# Power.net
KiCad netlist of a schematic drawn in Altium Designer
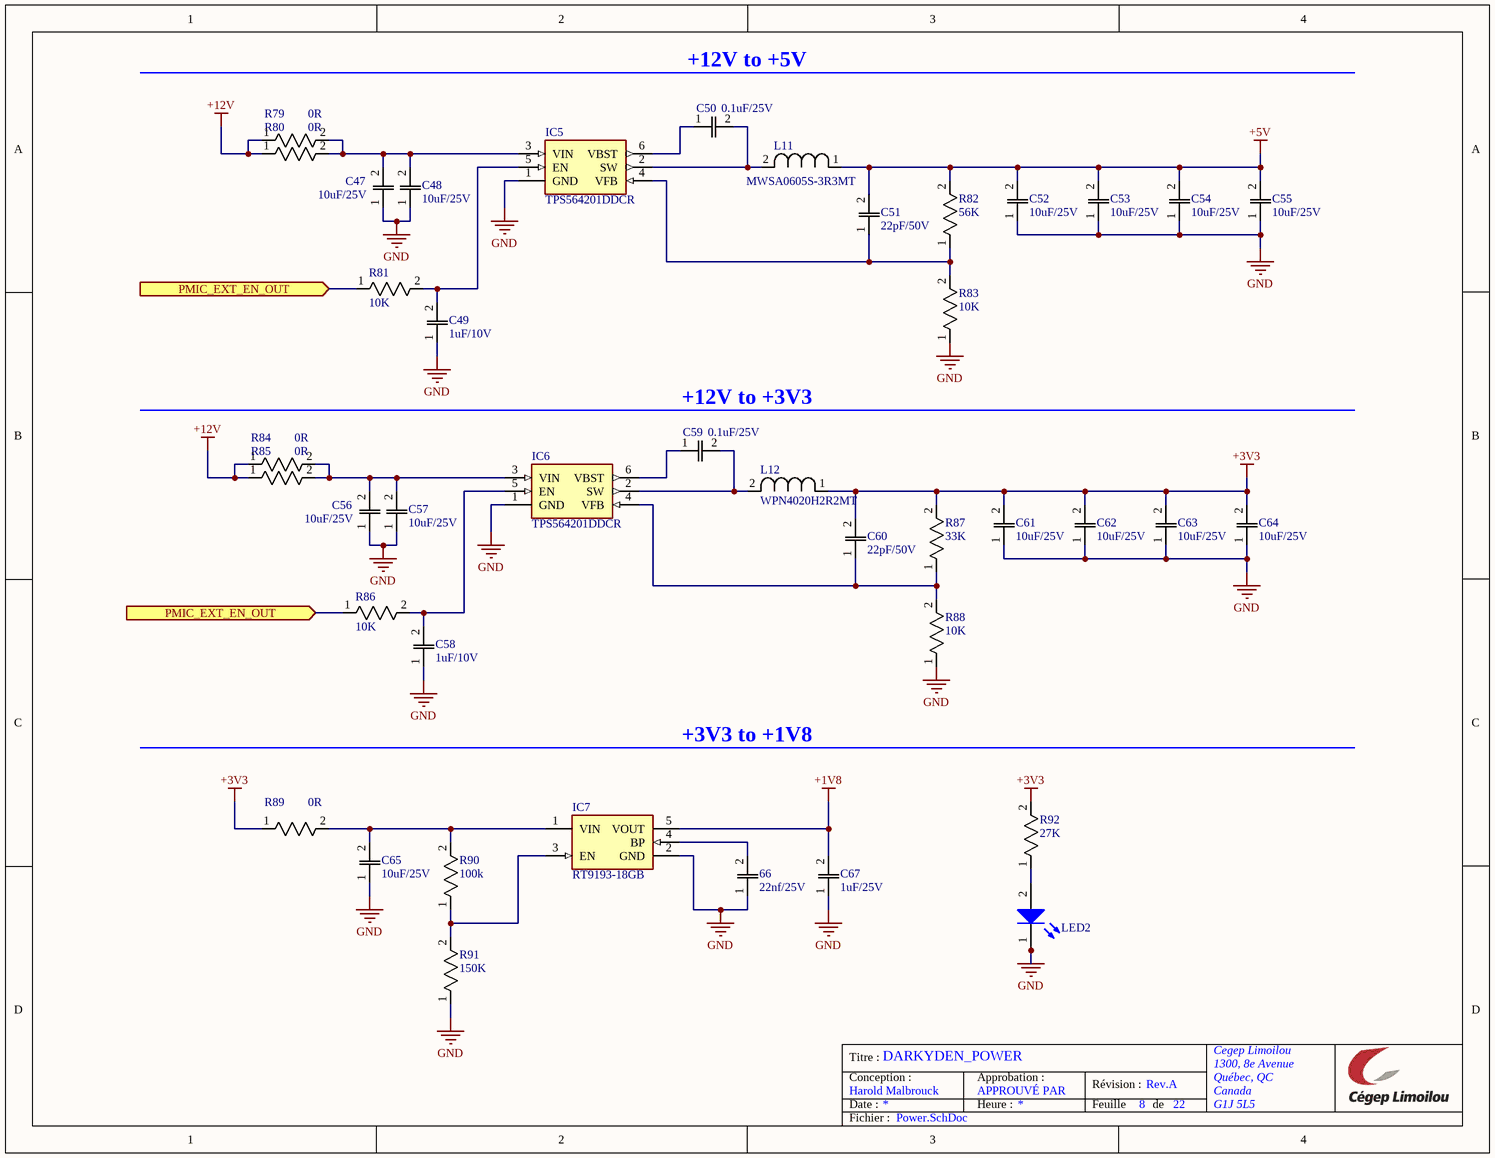
[diagram p0: Power.SchDoc]

(export (version "E")
  (design (tool "Eeschema 10.0.6"))
  (components
    (comp (ref "66")
      (value "22nf/25V")
      (footprint "SamacSys:C0805")
      (description "22nF, 25 V, 0805 [2012 Metric], 5%, C0G / NP0")
      (fields
        (field (name "MANUFACTURER_PART_NUMBER") "C0805C223J3GACTU")
        (field (name "MANUFACTURER") "KEMET")
      )
      (libsource (lib "SamacSys") (part "C0805C223J3GACTU"))
    )
    (comp (ref "C47")
      (value "10uF/25V")
      (footprint "CAPC220145_88N_KEM")
      (description "10uF / 25 VDC, +85degC, X5R Dielec, +/-10% ¦ KEMET C0805C106K3PACTU 0805")
      (fields
        (field (name "MANUFACTURER") "KEMET")
        (field (name "MANUFACTURER PART NUMBER") "C0805C106K3PACTU")
      )
      (libsource (lib "C0805C106K3PACTU") (part "C0805C106K3PACTU"))
    )
    (comp (ref "C48")
      (value "10uF/25V")
      (footprint "CAPC220145_88N_KEM")
      (description "10uF / 25 VDC, +85degC, X5R Dielec, +/-10% ¦ KEMET C0805C106K3PACTU 0805")
      (fields
        (field (name "MANUFACTURER") "KEMET")
        (field (name "MANUFACTURER PART NUMBER") "C0805C106K3PACTU")
      )
      (libsource (lib "C0805C106K3PACTU") (part "C0805C106K3PACTU"))
    )
    (comp (ref "C49")
      (value "1uF/10V")
      (footprint "CAPC220145_88N_KEM")
      (description "Multilayer Ceramic Capacitors MLCC - SMD/SMT 10V 1uF X7R 0805 10%")
      (fields
        (field (name "MANUFACTURER") "KEMET")
        (field (name "MANUFACTURER PART NUMBER") "C0805C105K8RACTU")
      )
      (libsource (lib "C0805C105K8RACTU") (part "C0805C105K8RACTU"))
    )
    (comp (ref "C50")
      (value "0.1uF/25V")
      (footprint "CAPC220145_88N_KEM")
      (description "0.1uF 25V X7R 10% SMD 0805 125C Plastic T/R")
      (fields
        (field (name "MANUFACTURER") "KEMET")
        (field (name "MANUFACTURER PART NUMBER") "C0805C104K3RACTU")
      )
      (libsource (lib "C0805C104K3RACTU") (part "C0805C104K3RACTU"))
    )
    (comp (ref "C51")
      (value "22pF/50V")
      (footprint "CAPC220145_88N_KEM")
      (description "Cap Ceramic 22pF 50V X7R 5% Pad SMD 0805 125°C T/R")
      (fields
        (field (name "MANUFACTURER") "KEMET")
        (field (name "MANUFACTURER PART NUMBER") "C0805C220J5RACTU")
      )
      (libsource (lib "C0805C220J5RACTU") (part "C0805C220J5RACTU"))
    )
    (comp (ref "C52")
      (value "10uF/25V")
      (footprint "CAPC220145_88N_KEM")
      (description "10uF / 25 VDC, +85degC, X5R Dielec, +/-10% ¦ KEMET C0805C106K3PACTU 0805")
      (fields
        (field (name "MANUFACTURER") "KEMET")
        (field (name "MANUFACTURER PART NUMBER") "C0805C106K3PACTU")
      )
      (libsource (lib "C0805C106K3PACTU") (part "C0805C106K3PACTU"))
    )
    (comp (ref "C53")
      (value "10uF/25V")
      (footprint "CAPC220145_88N_KEM")
      (description "10uF / 25 VDC, +85degC, X5R Dielec, +/-10% ¦ KEMET C0805C106K3PACTU 0805")
      (fields
        (field (name "MANUFACTURER") "KEMET")
        (field (name "MANUFACTURER PART NUMBER") "C0805C106K3PACTU")
      )
      (libsource (lib "C0805C106K3PACTU") (part "C0805C106K3PACTU"))
    )
    (comp (ref "C54")
      (value "10uF/25V")
      (footprint "CAPC220145_88N_KEM")
      (description "10uF / 25 VDC, +85degC, X5R Dielec, +/-10% ¦ KEMET C0805C106K3PACTU 0805")
      (fields
        (field (name "MANUFACTURER") "KEMET")
        (field (name "MANUFACTURER PART NUMBER") "C0805C106K3PACTU")
      )
      (libsource (lib "C0805C106K3PACTU") (part "C0805C106K3PACTU"))
    )
    (comp (ref "C55")
      (value "10uF/25V")
      (footprint "CAPC220145_88N_KEM")
      (description "10uF / 25 VDC, +85degC, X5R Dielec, +/-10% ¦ KEMET C0805C106K3PACTU 0805")
      (fields
        (field (name "MANUFACTURER") "KEMET")
        (field (name "MANUFACTURER PART NUMBER") "C0805C106K3PACTU")
      )
      (libsource (lib "C0805C106K3PACTU") (part "C0805C106K3PACTU"))
    )
    (comp (ref "C56")
      (value "10uF/25V")
      (footprint "CAPC220145_88N_KEM")
      (description "10uF / 25 VDC, +85degC, X5R Dielec, +/-10% ¦ KEMET C0805C106K3PACTU 0805")
      (fields
        (field (name "MANUFACTURER") "KEMET")
        (field (name "MANUFACTURER PART NUMBER") "C0805C106K3PACTU")
      )
      (libsource (lib "C0805C106K3PACTU") (part "C0805C106K3PACTU"))
    )
    (comp (ref "C57")
      (value "10uF/25V")
      (footprint "CAPC220145_88N_KEM")
      (description "10uF / 25 VDC, +85degC, X5R Dielec, +/-10% ¦ KEMET C0805C106K3PACTU 0805")
      (fields
        (field (name "MANUFACTURER") "KEMET")
        (field (name "MANUFACTURER PART NUMBER") "C0805C106K3PACTU")
      )
      (libsource (lib "C0805C106K3PACTU") (part "C0805C106K3PACTU"))
    )
    (comp (ref "C58")
      (value "1uF/10V")
      (footprint "CAPC220145_88N_KEM")
      (description "Multilayer Ceramic Capacitors MLCC - SMD/SMT 10V 1uF X7R 0805 10%")
      (fields
        (field (name "MANUFACTURER") "KEMET")
        (field (name "MANUFACTURER PART NUMBER") "C0805C105K8RACTU")
      )
      (libsource (lib "C0805C105K8RACTU") (part "C0805C105K8RACTU"))
    )
    (comp (ref "C59")
      (value "0.1uF/25V")
      (footprint "CAPC220145_88N_KEM")
      (description "0.1uF 25V X7R 10% SMD 0805 125C Plastic T/R")
      (fields
        (field (name "MANUFACTURER") "KEMET")
        (field (name "MANUFACTURER PART NUMBER") "C0805C104K3RACTU")
      )
      (libsource (lib "C0805C104K3RACTU") (part "C0805C104K3RACTU"))
    )
    (comp (ref "C60")
      (value "22pF/50V")
      (footprint "CAPC220145_88N_KEM")
      (description "Cap Ceramic 22pF 50V X7R 5% Pad SMD 0805 125°C T/R")
      (fields
        (field (name "MANUFACTURER") "KEMET")
        (field (name "MANUFACTURER PART NUMBER") "C0805C220J5RACTU")
      )
      (libsource (lib "C0805C220J5RACTU") (part "C0805C220J5RACTU"))
    )
    (comp (ref "C61")
      (value "10uF/25V")
      (footprint "CAPC220145_88N_KEM")
      (description "10uF / 25 VDC, +85degC, X5R Dielec, +/-10% ¦ KEMET C0805C106K3PACTU 0805")
      (fields
        (field (name "MANUFACTURER") "KEMET")
        (field (name "MANUFACTURER PART NUMBER") "C0805C106K3PACTU")
      )
      (libsource (lib "C0805C106K3PACTU") (part "C0805C106K3PACTU"))
    )
    (comp (ref "C62")
      (value "10uF/25V")
      (footprint "CAPC220145_88N_KEM")
      (description "10uF / 25 VDC, +85degC, X5R Dielec, +/-10% ¦ KEMET C0805C106K3PACTU 0805")
      (fields
        (field (name "MANUFACTURER") "KEMET")
        (field (name "MANUFACTURER PART NUMBER") "C0805C106K3PACTU")
      )
      (libsource (lib "C0805C106K3PACTU") (part "C0805C106K3PACTU"))
    )
    (comp (ref "C63")
      (value "10uF/25V")
      (footprint "CAPC220145_88N_KEM")
      (description "10uF / 25 VDC, +85degC, X5R Dielec, +/-10% ¦ KEMET C0805C106K3PACTU 0805")
      (fields
        (field (name "MANUFACTURER") "KEMET")
        (field (name "MANUFACTURER PART NUMBER") "C0805C106K3PACTU")
      )
      (libsource (lib "C0805C106K3PACTU") (part "C0805C106K3PACTU"))
    )
    (comp (ref "C64")
      (value "10uF/25V")
      (footprint "CAPC220145_88N_KEM")
      (description "10uF / 25 VDC, +85degC, X5R Dielec, +/-10% ¦ KEMET C0805C106K3PACTU 0805")
      (fields
        (field (name "MANUFACTURER") "KEMET")
        (field (name "MANUFACTURER PART NUMBER") "C0805C106K3PACTU")
      )
      (libsource (lib "C0805C106K3PACTU") (part "C0805C106K3PACTU"))
    )
    (comp (ref "C65")
      (value "10uF/25V")
      (footprint "CAPC220145_88N_KEM")
      (description "10uF / 25 VDC, +85degC, X5R Dielec, +/-10% ¦ KEMET C0805C106K3PACTU 0805")
      (fields
        (field (name "MANUFACTURER") "KEMET")
        (field (name "MANUFACTURER PART NUMBER") "C0805C106K3PACTU")
      )
      (libsource (lib "C0805C106K3PACTU") (part "C0805C106K3PACTU"))
    )
    (comp (ref "C67")
      (value "1uF/25V")
      (footprint "SamacSys:C0805")
      (description "1 µF, 25 V (DC), ±10 %, SMD 0805, X7R, C0805C105K3RAC7800")
      (fields
        (field (name "MANUFACTURER_PART_NUMBER") "C0805C105K3RACTU")
        (field (name "MOUSER PART NUMBER") "80-C0805C105K3R")
      )
      (libsource (lib "SamacSys") (part "C0805C105K3RACTU"))
    )
    (comp (ref "IC5")
      (value "TPS564201DDCR")
      (footprint "SamacSys:SOT95P280X110-6N")
      (fields
        (field (name "MOUSER PART NUMBER") "595-TPS564201DDCR")
        (field (name "MANUFACTURER") "Texas Instruments")
      )
      (libsource (lib "SamacSys") (part "TPS564201DDCR"))
    )
    (comp (ref "IC6")
      (value "TPS564201DDCR")
      (footprint "SamacSys:SOT95P280X110-6N")
      (fields
        (field (name "MOUSER PART NUMBER") "595-TPS564201DDCR")
        (field (name "MANUFACTURER") "Texas Instruments")
      )
      (libsource (lib "SamacSys") (part "TPS564201DDCR"))
    )
    (comp (ref "IC7")
      (value "RT9193-18GB")
      (footprint "SamacSys:SOT94P279X130-5N")
      (description "Linear Voltage Regulator IC Positive Fixed 1.8V Output 300mA SOT-23-5")
      (fields (field (name "MOUSER PART NUMBER") "835-RT9193-18GB"))
      (libsource (lib "SamacSys") (part "RT9193-18GB"))
    )
    (comp (ref "L11")
      (value "MWSA0605S-3R3MT")
      (footprint "IND_MWSA0603S_SNL")
      (description "3.3 µH Shielded Drum Core, Wirewound Inductor 8.5 A 22mOhm Max Nonstandard")
      (libsource (lib "MWSA0603S-XRXMT") (part "MWSA0605S-3R3MT"))
    )
    (comp (ref "L12")
      (value "WPN4020H2R2MT")
      (footprint "IND_WPN4020H_SNL")
      (description "2.2 µH Shielded Drum Core, Wirewound Inductor 4.3 A 48mOhm Max Nonstandard")
      (fields (field (name "MANUFACTURER") "Sunlord"))
      (libsource (lib "WPN4020H2R2MT") (part "WPN4020H2R2MT"))
    )
    (comp (ref "LED2")
      (value "Blue, 3.2V, 140°")
      (footprint "WL-SMCD_0603")
      (description "WL-SMCD Mono-color Chip LED Diffused, SMT, size 0603, Blue, 3.2V, 140°")
      (fields
        (field (name "MANUFACTURER PART NUMBER") "150060BS55040")
        (field (name "MANUFACTURER") "Wurth Elektronik")
      )
      (libsource (lib "0603_LED") (part "BLUE"))
    )
    (comp (ref "R79")
      (value "0R")
      (footprint "SamacSys:ERJ3EKF1000V")
      (description "Zero Ohm Resistor, Jumper, 0603 [1608 Metric], Thick Film, 100 mW, 1 A, Surface Mount")
      (fields
        (field (name "MANUFACTURER_PART_NUMBER") "ERJ-3GEY0R00V")
        (field (name "MOUSER PART NUMBER") "667-ERJ-3GEY0R00V")
      )
      (libsource (lib "SamacSys") (part "ERJ-3GEY0R00V"))
    )
    (comp (ref "R80")
      (value "0R")
      (footprint "SamacSys:ERJ3EKF1000V")
      (description "Zero Ohm Resistor, Jumper, 0603 [1608 Metric], Thick Film, 100 mW, 1 A, Surface Mount")
      (fields
        (field (name "MANUFACTURER_PART_NUMBER") "ERJ-3GEY0R00V")
        (field (name "MOUSER PART NUMBER") "667-ERJ-3GEY0R00V")
      )
      (libsource (lib "SamacSys") (part "ERJ-3GEY0R00V"))
    )
    (comp (ref "R81")
      (value "10K")
      (footprint "SamacSys:ERJ3EKF1000V")
      (description "10K Ohm 5% Res Thick Film 0603  0.1W(1/10W) ±200ppm/C Pad SMD Automotive T/R")
      (fields
        (field (name "MANUFACTURER_PART_NUMBER") "ERJ-3GEYJ103V")
        (field (name "MOUSER PART NUMBER") "667-ERJ-3GEYJ103V")
      )
      (libsource (lib "SamacSys") (part "ERJ-3GEYJ103V"))
    )
    (comp (ref "R82")
      (value "56K")
      (footprint "SamacSys:RESC1608X55N")
      (description "56K Ohm 1% 1/10W +/-100ppm/ßC Molded SMD Punched Carrier T/R")
      (fields
        (field (name "MANUFACTURER_PART_NUMBER") "ERJ-3EKF5602V")
        (field (name "MOUSER PART NUMBER") "667-ERJ-3EKF5602V")
      )
      (libsource (lib "SamacSys") (part "ERJ-3EKF5602V"))
    )
    (comp (ref "R83")
      (value "10K")
      (footprint "SamacSys:ERJ3EKF1000V")
      (description "10K Ohm 5% Res Thick Film 0603  0.1W(1/10W) ±200ppm/C Pad SMD Automotive T/R")
      (fields
        (field (name "MANUFACTURER_PART_NUMBER") "ERJ-3GEYJ103V")
        (field (name "MOUSER PART NUMBER") "667-ERJ-3GEYJ103V")
      )
      (libsource (lib "SamacSys") (part "ERJ-3GEYJ103V"))
    )
    (comp (ref "R84")
      (value "0R")
      (footprint "SamacSys:ERJ3EKF1000V")
      (description "Zero Ohm Resistor, Jumper, 0603 [1608 Metric], Thick Film, 100 mW, 1 A, Surface Mount")
      (fields
        (field (name "MANUFACTURER_PART_NUMBER") "ERJ-3GEY0R00V")
        (field (name "MOUSER PART NUMBER") "667-ERJ-3GEY0R00V")
      )
      (libsource (lib "SamacSys") (part "ERJ-3GEY0R00V"))
    )
    (comp (ref "R85")
      (value "0R")
      (footprint "SamacSys:ERJ3EKF1000V")
      (description "Zero Ohm Resistor, Jumper, 0603 [1608 Metric], Thick Film, 100 mW, 1 A, Surface Mount")
      (fields
        (field (name "MANUFACTURER_PART_NUMBER") "ERJ-3GEY0R00V")
        (field (name "MOUSER PART NUMBER") "667-ERJ-3GEY0R00V")
      )
      (libsource (lib "SamacSys") (part "ERJ-3GEY0R00V"))
    )
    (comp (ref "R86")
      (value "10K")
      (footprint "SamacSys:ERJ3EKF1000V")
      (description "10K Ohm 5% Res Thick Film 0603  0.1W(1/10W) ±200ppm/C Pad SMD Automotive T/R")
      (fields
        (field (name "MANUFACTURER_PART_NUMBER") "ERJ-3GEYJ103V")
        (field (name "MOUSER PART NUMBER") "667-ERJ-3GEYJ103V")
      )
      (libsource (lib "SamacSys") (part "ERJ-3GEYJ103V"))
    )
    (comp (ref "R87")
      (value "33K")
      (footprint "SamacSys:ERJ3EKF1000V")
      (description "33K Ohm 0603  5% 0.1W(1/10W) +/-200ppm/ßC SMD Automotive T/R")
      (fields
        (field (name "MANUFACTURER_PART_NUMBER") "ERJ-3GEYJ333V")
        (field (name "MOUSER PART NUMBER") "667-ERJ-3GEYJ333V")
      )
      (libsource (lib "SamacSys") (part "ERJ-3GEYJ333V"))
    )
    (comp (ref "R88")
      (value "10K")
      (footprint "SamacSys:ERJ3EKF1000V")
      (description "10K Ohm 5% Res Thick Film 0603  0.1W(1/10W) ±200ppm/C Pad SMD Automotive T/R")
      (fields
        (field (name "MANUFACTURER_PART_NUMBER") "ERJ-3GEYJ103V")
        (field (name "MOUSER PART NUMBER") "667-ERJ-3GEYJ103V")
      )
      (libsource (lib "SamacSys") (part "ERJ-3GEYJ103V"))
    )
    (comp (ref "R89")
      (value "0R")
      (footprint "SamacSys:ERJ3EKF1000V")
      (description "Zero Ohm Resistor, Jumper, 0603 [1608 Metric], Thick Film, 100 mW, 1 A, Surface Mount")
      (fields
        (field (name "MANUFACTURER_PART_NUMBER") "ERJ-3GEY0R00V")
        (field (name "MOUSER PART NUMBER") "667-ERJ-3GEY0R00V")
      )
      (libsource (lib "SamacSys") (part "ERJ-3GEY0R00V"))
    )
    (comp (ref "R90")
      (value "100k")
      (footprint "SamacSys:ERJ3EKF1000V")
      (description "100K Ohm 5%  Res Thick Film 0603 1/10W +/-200ppm/ßC Molded SMD Punched Carrier T/R")
      (fields
        (field (name "MANUFACTURER_PART_NUMBER") "ERJ-3GEYJ104V")
        (field (name "MOUSER PART NUMBER") "667-ERJ-3GEYJ104V")
      )
      (libsource (lib "SamacSys") (part "ERJ-3GEYJ104V"))
    )
    (comp (ref "R91")
      (value "150K")
      (footprint "SamacSys:ERJ3EKF1000V")
      (description "150 kOhm, ± 5%, 100 mW, 0603 [1608 Metric], Thick Film, General Purpose")
      (fields
        (field (name "MANUFACTURER_PART_NUMBER") "ERJ-3GEYJ154V")
        (field (name "MOUSER PART NUMBER") "667-ERJ-3GEYJ154V")
      )
      (libsource (lib "SamacSys") (part "ERJ-3GEYJ154V"))
    )
    (comp (ref "R92")
      (value "27K")
      (footprint "RC0603N_PAN")
      (description "Res Thick Film 0603 27K Ohm 1% 1/10W ±100ppm/°C Molded SMD Punched Carrier T/R")
      (fields
        (field (name "MANUFACTURER") "Panasonic")
        (field (name "MANUFACTURER PART NUMBER") "ERJ-3EKF2702V")
      )
      (libsource (lib "ERJ-3EKF2702V") (part "ERJ-3EKF2702V"))
    )
  )
  (nets
    (net (code "1") (name "+1V8") (class "Default")
      (node (ref "C67") (pin "2") (pinfunction "2_2") (pintype "passive"))
      (node (ref "IC7") (pin "5") (pinfunction "VOUT_5") (pintype "power_in"))
    )
    (net (code "2") (name "+3V3") (class "Default")
      (node (ref "C60") (pin "2") (pinfunction "2_2") (pintype "passive"))
      (node (ref "C61") (pin "2") (pinfunction "2_2") (pintype "passive"))
      (node (ref "C62") (pin "2") (pinfunction "2_2") (pintype "passive"))
      (node (ref "C63") (pin "2") (pinfunction "2_2") (pintype "passive"))
      (node (ref "C64") (pin "2") (pinfunction "2_2") (pintype "passive"))
      (node (ref "L12") (pin "1") (pinfunction "1_1") (pintype "passive"))
      (node (ref "R87") (pin "2") (pinfunction "2_2") (pintype "passive"))
      (node (ref "R89") (pin "1") (pinfunction "1_1") (pintype "passive"))
      (node (ref "R92") (pin "2") (pinfunction "2_2") (pintype "passive"))
    )
    (net (code "3") (name "+5V") (class "Default")
      (node (ref "C51") (pin "2") (pinfunction "2_2") (pintype "passive"))
      (node (ref "C52") (pin "2") (pinfunction "2_2") (pintype "passive"))
      (node (ref "C53") (pin "2") (pinfunction "2_2") (pintype "passive"))
      (node (ref "C54") (pin "2") (pinfunction "2_2") (pintype "passive"))
      (node (ref "C55") (pin "2") (pinfunction "2_2") (pintype "passive"))
      (node (ref "L11") (pin "1") (pinfunction "1_1") (pintype "passive"))
      (node (ref "R82") (pin "2") (pinfunction "2_2") (pintype "passive"))
    )
    (net (code "4") (name "+12V") (class "Default")
      (node (ref "R79") (pin "1") (pinfunction "1_1") (pintype "passive"))
      (node (ref "R80") (pin "1") (pinfunction "1_1") (pintype "passive"))
      (node (ref "R84") (pin "1") (pinfunction "1_1") (pintype "passive"))
      (node (ref "R85") (pin "1") (pinfunction "1_1") (pintype "passive"))
    )
    (net (code "5") (name "/PMIC_EXT_EN_OUT") (class "Default")
      (node (ref "R81") (pin "1") (pinfunction "1_1") (pintype "passive"))
      (node (ref "R86") (pin "1") (pinfunction "1_1") (pintype "passive"))
    )
    (net (code "6") (name "GND") (class "Default")
      (node (ref "66") (pin "1") (pinfunction "1_1") (pintype "passive"))
      (node (ref "C47") (pin "1") (pinfunction "1_1") (pintype "passive"))
      (node (ref "C48") (pin "1") (pinfunction "1_1") (pintype "passive"))
      (node (ref "C49") (pin "1") (pinfunction "1_1") (pintype "passive"))
      (node (ref "C52") (pin "1") (pinfunction "1_1") (pintype "passive"))
      (node (ref "C53") (pin "1") (pinfunction "1_1") (pintype "passive"))
      (node (ref "C54") (pin "1") (pinfunction "1_1") (pintype "passive"))
      (node (ref "C55") (pin "1") (pinfunction "1_1") (pintype "passive"))
      (node (ref "C56") (pin "1") (pinfunction "1_1") (pintype "passive"))
      (node (ref "C57") (pin "1") (pinfunction "1_1") (pintype "passive"))
      (node (ref "C58") (pin "1") (pinfunction "1_1") (pintype "passive"))
      (node (ref "C61") (pin "1") (pinfunction "1_1") (pintype "passive"))
      (node (ref "C62") (pin "1") (pinfunction "1_1") (pintype "passive"))
      (node (ref "C63") (pin "1") (pinfunction "1_1") (pintype "passive"))
      (node (ref "C64") (pin "1") (pinfunction "1_1") (pintype "passive"))
      (node (ref "C65") (pin "1") (pinfunction "1_1") (pintype "passive"))
      (node (ref "C67") (pin "1") (pinfunction "1_1") (pintype "passive"))
      (node (ref "IC5") (pin "1") (pinfunction "GND_1") (pintype "passive"))
      (node (ref "IC6") (pin "1") (pinfunction "GND_1") (pintype "passive"))
      (node (ref "IC7") (pin "2") (pinfunction "GND_2") (pintype "passive"))
      (node (ref "LED2") (pin "1") (pinfunction "K_1") (pintype "passive"))
      (node (ref "R83") (pin "1") (pinfunction "1_1") (pintype "passive"))
      (node (ref "R88") (pin "1") (pinfunction "1_1") (pintype "passive"))
      (node (ref "R91") (pin "1") (pinfunction "1_1") (pintype "passive"))
    )
    (net (code "7") (name "Net-(IC5-EN)") (class "Default")
      (node (ref "C49") (pin "2") (pinfunction "2_2") (pintype "passive"))
      (node (ref "IC5") (pin "5") (pinfunction "EN_5") (pintype "input"))
      (node (ref "R81") (pin "2") (pinfunction "2_2") (pintype "passive"))
    )
    (net (code "8") (name "Net-(IC5-SW)") (class "Default")
      (node (ref "C50") (pin "2") (pinfunction "2_2") (pintype "passive"))
      (node (ref "IC5") (pin "2") (pinfunction "SW_2") (pintype "output"))
      (node (ref "L11") (pin "2") (pinfunction "2_2") (pintype "passive"))
    )
    (net (code "9") (name "Net-(IC5-VBST)") (class "Default")
      (node (ref "C50") (pin "1") (pinfunction "1_1") (pintype "passive"))
      (node (ref "IC5") (pin "6") (pinfunction "VBST_6") (pintype "output"))
    )
    (net (code "10") (name "Net-(IC5-VFB)") (class "Default")
      (node (ref "C51") (pin "1") (pinfunction "1_1") (pintype "passive"))
      (node (ref "IC5") (pin "4") (pinfunction "VFB_4") (pintype "input"))
      (node (ref "R82") (pin "1") (pinfunction "1_1") (pintype "passive"))
      (node (ref "R83") (pin "2") (pinfunction "2_2") (pintype "passive"))
    )
    (net (code "11") (name "Net-(IC5-VIN)") (class "Default")
      (node (ref "C47") (pin "2") (pinfunction "2_2") (pintype "passive"))
      (node (ref "C48") (pin "2") (pinfunction "2_2") (pintype "passive"))
      (node (ref "IC5") (pin "3") (pinfunction "VIN_3") (pintype "input"))
      (node (ref "R79") (pin "2") (pinfunction "2_2") (pintype "passive"))
      (node (ref "R80") (pin "2") (pinfunction "2_2") (pintype "passive"))
    )
    (net (code "12") (name "Net-(IC6-EN)") (class "Default")
      (node (ref "C58") (pin "2") (pinfunction "2_2") (pintype "passive"))
      (node (ref "IC6") (pin "5") (pinfunction "EN_5") (pintype "input"))
      (node (ref "R86") (pin "2") (pinfunction "2_2") (pintype "passive"))
    )
    (net (code "13") (name "Net-(IC6-SW)") (class "Default")
      (node (ref "C59") (pin "2") (pinfunction "2_2") (pintype "passive"))
      (node (ref "IC6") (pin "2") (pinfunction "SW_2") (pintype "output"))
      (node (ref "L12") (pin "2") (pinfunction "2_2") (pintype "passive"))
    )
    (net (code "14") (name "Net-(IC6-VBST)") (class "Default")
      (node (ref "C59") (pin "1") (pinfunction "1_1") (pintype "passive"))
      (node (ref "IC6") (pin "6") (pinfunction "VBST_6") (pintype "output"))
    )
    (net (code "15") (name "Net-(IC6-VFB)") (class "Default")
      (node (ref "C60") (pin "1") (pinfunction "1_1") (pintype "passive"))
      (node (ref "IC6") (pin "4") (pinfunction "VFB_4") (pintype "input"))
      (node (ref "R87") (pin "1") (pinfunction "1_1") (pintype "passive"))
      (node (ref "R88") (pin "2") (pinfunction "2_2") (pintype "passive"))
    )
    (net (code "16") (name "Net-(IC6-VIN)") (class "Default")
      (node (ref "C56") (pin "2") (pinfunction "2_2") (pintype "passive"))
      (node (ref "C57") (pin "2") (pinfunction "2_2") (pintype "passive"))
      (node (ref "IC6") (pin "3") (pinfunction "VIN_3") (pintype "input"))
      (node (ref "R84") (pin "2") (pinfunction "2_2") (pintype "passive"))
      (node (ref "R85") (pin "2") (pinfunction "2_2") (pintype "passive"))
    )
    (net (code "17") (name "Net-(IC7-BP)") (class "Default")
      (node (ref "66") (pin "2") (pinfunction "2_2") (pintype "passive"))
      (node (ref "IC7") (pin "4") (pinfunction "BP_4") (pintype "input"))
    )
    (net (code "18") (name "Net-(IC7-EN)") (class "Default")
      (node (ref "IC7") (pin "3") (pinfunction "EN_3") (pintype "input"))
      (node (ref "R90") (pin "1") (pinfunction "1_1") (pintype "passive"))
      (node (ref "R91") (pin "2") (pinfunction "2_2") (pintype "passive"))
    )
    (net (code "19") (name "Net-(IC7-VIN)") (class "Default")
      (node (ref "C65") (pin "2") (pinfunction "2_2") (pintype "passive"))
      (node (ref "IC7") (pin "1") (pinfunction "VIN_1") (pintype "power_in"))
      (node (ref "R89") (pin "2") (pinfunction "2_2") (pintype "passive"))
      (node (ref "R90") (pin "2") (pinfunction "2_2") (pintype "passive"))
    )
    (net (code "20") (name "Net-(LED2-A)") (class "Default")
      (node (ref "LED2") (pin "2") (pinfunction "A_2") (pintype "passive"))
      (node (ref "R92") (pin "1") (pinfunction "1_1") (pintype "passive"))
    )
  )
)
